# eth2dmx.net
KiCad netlist of a schematic drawn in EAGLE
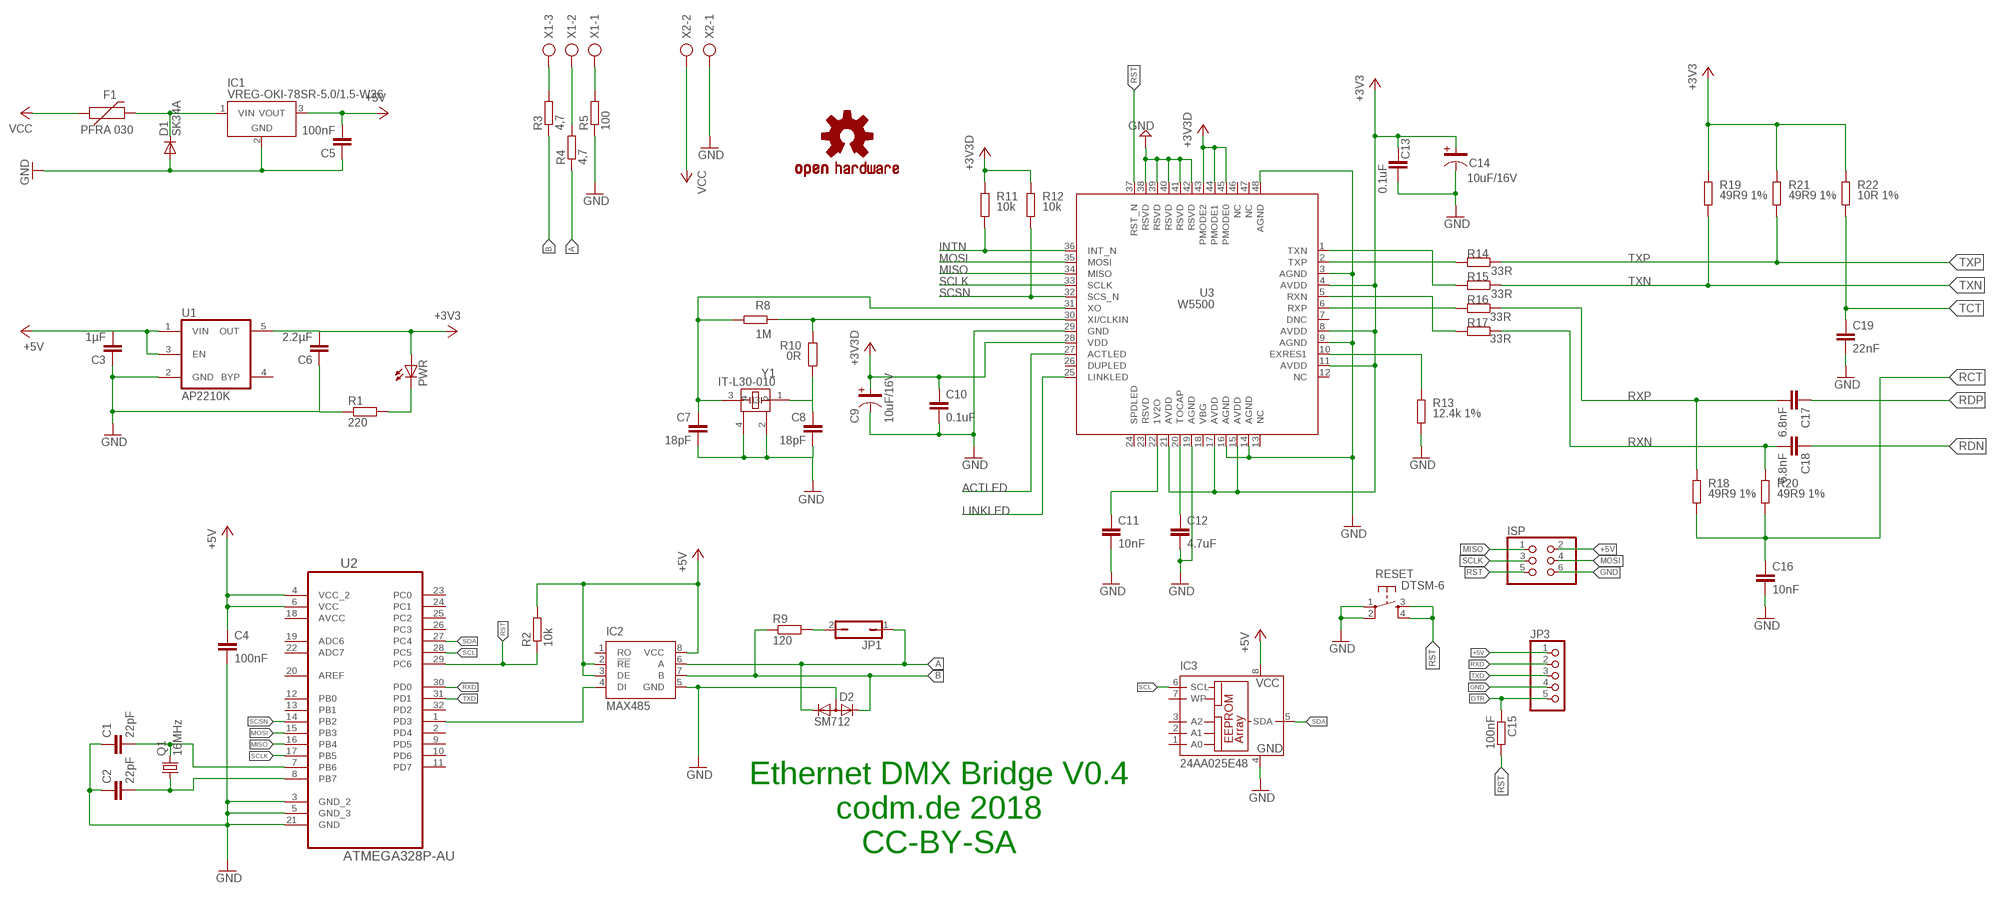
[diagram p0: schematic, sheet 1, part 1 of 2]
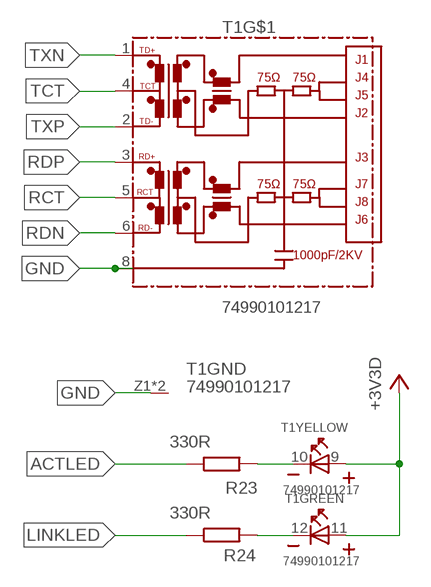
[diagram p1: schematic, sheet 1, part 2 of 2]

(export (version "E")
  (design (tool "Eeschema 10.0.6"))
  (components
    (comp (ref "C1")
      (value "22pF")
      (footprint "eagle-import:C0805")
      (libsource (lib "eagle-import") (part "C-EUC0805"))
    )
    (comp (ref "C2")
      (value "22pF")
      (footprint "eagle-import:C0805")
      (libsource (lib "eagle-import") (part "C-EUC0805"))
    )
    (comp (ref "C3")
      (value "1µF")
      (footprint "eagle-import:C0805")
      (libsource (lib "eagle-import") (part "C-EUC0805"))
    )
    (comp (ref "C4")
      (value "100nF")
      (footprint "eagle-import:C0805")
      (libsource (lib "eagle-import") (part "C-EUC0805"))
    )
    (comp (ref "C5")
      (value "100nF")
      (footprint "eagle-import:C0805")
      (libsource (lib "eagle-import") (part "C-EUC0805"))
    )
    (comp (ref "C6")
      (value "2.2µF")
      (footprint "eagle-import:C0805")
      (libsource (lib "eagle-import") (part "C-EUC0805"))
    )
    (comp (ref "C7")
      (value "18pF")
      (footprint "eagle-import:C0805")
      (libsource (lib "eagle-import") (part "C-EUC0805"))
    )
    (comp (ref "C8")
      (value "18pF")
      (footprint "eagle-import:C0805")
      (libsource (lib "eagle-import") (part "C-EUC0805"))
    )
    (comp (ref "C9")
      (value "10uF/16V")
      (footprint "eagle-import:C-3216(TANTAL)")
      (libsource (lib "eagle-import") (part "C-3216(TANTAL)"))
    )
    (comp (ref "C10")
      (value "0.1uF")
      (footprint "eagle-import:C0805")
      (libsource (lib "eagle-import") (part "C-EUC0805"))
    )
    (comp (ref "C11")
      (value "10nF")
      (footprint "eagle-import:C0805")
      (libsource (lib "eagle-import") (part "C-EUC0805"))
    )
    (comp (ref "C12")
      (value "4.7uF")
      (footprint "eagle-import:C0805")
      (libsource (lib "eagle-import") (part "C-EUC0805"))
    )
    (comp (ref "C13")
      (value "0.1uF")
      (footprint "eagle-import:C0805")
      (libsource (lib "eagle-import") (part "C-EUC0805"))
    )
    (comp (ref "C14")
      (value "10uF/16V")
      (footprint "eagle-import:C-3216(TANTAL)")
      (libsource (lib "eagle-import") (part "C-3216(TANTAL)"))
    )
    (comp (ref "C15")
      (value "100nF")
      (footprint "eagle-import:R0805")
      (libsource (lib "eagle-import") (part "R-EU_R0805"))
    )
    (comp (ref "C16")
      (value "10nF")
      (footprint "eagle-import:C0805")
      (libsource (lib "eagle-import") (part "C-EUC0805"))
    )
    (comp (ref "C17")
      (value "6.8nF")
      (footprint "eagle-import:C0805")
      (libsource (lib "eagle-import") (part "C-EUC0805"))
    )
    (comp (ref "C18")
      (value "6.8nF")
      (footprint "eagle-import:C0805")
      (libsource (lib "eagle-import") (part "C-EUC0805"))
    )
    (comp (ref "C19")
      (value "22nF")
      (footprint "eagle-import:C0805")
      (libsource (lib "eagle-import") (part "C-EUC0805"))
    )
    (comp (ref "D1")
      (value "SK34A")
      (footprint "eagle-import:DO214AC")
      (libsource (lib "eagle-import") (part "DIODE-DO214AC"))
    )
    (comp (ref "D2")
      (value "SM712")
      (footprint "eagle-import:SOT23")
      (libsource (lib "eagle-import") (part "DIODE-2CA|ACSOT23"))
    )
    (comp (ref "F1")
      (value "PFRA 030")
      (footprint "eagle-import:PTH")
      (libsource (lib "eagle-import") (part "PPTC_PTH"))
    )
    (comp (ref "IC1")
      (value "VREG-OKI-78SR-5.0/1.5-W36")
      (footprint "eagle-import:OKI-78SR")
      (libsource (lib "eagle-import") (part "VREG-OKI-78SR-5.0/1.5-W36"))
    )
    (comp (ref "IC2")
      (value "MAX485")
      (footprint "eagle-import:SOIC8")
      (libsource (lib "eagle-import") (part "LTC485S"))
    )
    (comp (ref "IC3")
      (value "24AA025E48")
      (footprint "eagle-import:SO-08")
      (fields (field (name "MPN") "24AA02/SN"))
      (libsource (lib "eagle-import") (part "24SNAA02"))
    )
    (comp (ref "ISP")
      (value "PINHD-2X3")
      (footprint "eagle-import:2X03")
      (libsource (lib "eagle-import") (part "PINHD-2X3"))
    )
    (comp (ref "JP1")
      (value "JP1Q")
      (footprint "eagle-import:JP1")
      (libsource (lib "eagle-import") (part "JP1Q"))
    )
    (comp (ref "JP3")
      (value "PINHD-1X5")
      (footprint "eagle-import:1X05")
      (libsource (lib "eagle-import") (part "PINHD-1X5"))
    )
    (comp (ref "LOGO1")
      (value "OSHW-LOGOM")
      (footprint "eagle-import:OSHW-LOGO-M")
      (libsource (lib "eagle-import") (part "OSHW-LOGOM"))
    )
    (comp (ref "PWR")
      (value "LEDCHIP-LED0805")
      (footprint "eagle-import:CHIP-LED0805")
      (libsource (lib "eagle-import") (part "LEDCHIP-LED0805"))
    )
    (comp (ref "Q1")
      (value "16MHz")
      (footprint "eagle-import:HC49U70")
      (libsource (lib "eagle-import") (part "CRYSTALHC49U70"))
    )
    (comp (ref "R1")
      (value "220")
      (footprint "eagle-import:R0805")
      (libsource (lib "eagle-import") (part "R-EU_R0805"))
    )
    (comp (ref "R2")
      (value "10k")
      (footprint "eagle-import:R0805")
      (libsource (lib "eagle-import") (part "R-EU_R0805"))
    )
    (comp (ref "R3")
      (value "4,7")
      (footprint "eagle-import:R0805")
      (libsource (lib "eagle-import") (part "R-EU_R0805"))
    )
    (comp (ref "R4")
      (value "4,7")
      (footprint "eagle-import:R0805")
      (libsource (lib "eagle-import") (part "R-EU_R0805"))
    )
    (comp (ref "R5")
      (value "100")
      (footprint "eagle-import:R0805")
      (libsource (lib "eagle-import") (part "R-EU_R0805"))
    )
    (comp (ref "R8")
      (value "1M")
      (footprint "eagle-import:R0805")
      (libsource (lib "eagle-import") (part "R-EU_R0805"))
    )
    (comp (ref "R9")
      (value "120")
      (footprint "eagle-import:R0805")
      (libsource (lib "eagle-import") (part "R-EU_R0805"))
    )
    (comp (ref "R10")
      (value "0R")
      (footprint "eagle-import:R0805")
      (libsource (lib "eagle-import") (part "R-EU_R0805"))
    )
    (comp (ref "R11")
      (value "10k")
      (footprint "eagle-import:R0805")
      (libsource (lib "eagle-import") (part "R-EU_R0805"))
    )
    (comp (ref "R12")
      (value "10k")
      (footprint "eagle-import:R0805")
      (libsource (lib "eagle-import") (part "R-EU_R0805"))
    )
    (comp (ref "R13")
      (value "12.4k 1%")
      (footprint "eagle-import:R0805")
      (libsource (lib "eagle-import") (part "R-EU_R0805"))
    )
    (comp (ref "R14")
      (value "33R")
      (footprint "eagle-import:R0805")
      (libsource (lib "eagle-import") (part "R-EU_R0805"))
    )
    (comp (ref "R15")
      (value "33R")
      (footprint "eagle-import:R0805")
      (libsource (lib "eagle-import") (part "R-EU_R0805"))
    )
    (comp (ref "R16")
      (value "33R")
      (footprint "eagle-import:R0805")
      (libsource (lib "eagle-import") (part "R-EU_R0805"))
    )
    (comp (ref "R17")
      (value "33R")
      (footprint "eagle-import:R0805")
      (libsource (lib "eagle-import") (part "R-EU_R0805"))
    )
    (comp (ref "R18")
      (value "49R9 1%")
      (footprint "eagle-import:R0805")
      (libsource (lib "eagle-import") (part "R-EU_R0805"))
    )
    (comp (ref "R19")
      (value "49R9 1%")
      (footprint "eagle-import:R0805")
      (libsource (lib "eagle-import") (part "R-EU_R0805"))
    )
    (comp (ref "R20")
      (value "49R9 1%")
      (footprint "eagle-import:R0805")
      (libsource (lib "eagle-import") (part "R-EU_R0805"))
    )
    (comp (ref "R21")
      (value "49R9 1%")
      (footprint "eagle-import:R0805")
      (libsource (lib "eagle-import") (part "R-EU_R0805"))
    )
    (comp (ref "R22")
      (value "10R 1%")
      (footprint "eagle-import:R0805")
      (libsource (lib "eagle-import") (part "R-EU_R0805"))
    )
    (comp (ref "R23")
      (value "330R")
      (footprint "eagle-import:R0805")
      (libsource (lib "eagle-import") (part "R-EU_R0805"))
    )
    (comp (ref "R24")
      (value "330R")
      (footprint "eagle-import:R0805")
      (libsource (lib "eagle-import") (part "R-EU_R0805"))
    )
    (comp (ref "RESET")
      (value "DTSM-6")
      (footprint "eagle-import:DTSM-6")
      (libsource (lib "eagle-import") (part "DTSM-6"))
    )
    (comp (ref "T1")
      (value "74990101217")
      (footprint "eagle-import:74990111217")
      (libsource (lib "eagle-import") (part "WE-RJ45_74990111217"))
    )
    (comp (ref "U1")
      (value "AP2210K")
      (footprint "eagle-import:SOT23-5")
      (libsource (lib "eagle-import") (part "AP2210K"))
    )
    (comp (ref "U2")
      (value "ATMEGA328P-AU")
      (footprint "eagle-import:QFP80P900X900X120-32N")
      (libsource (lib "eagle-import") (part "ATMEGA328P-AU"))
    )
    (comp (ref "U3")
      (value "W5500")
      (footprint "eagle-import:W5500")
      (libsource (lib "eagle-import") (part "W5500"))
    )
    (comp (ref "X1")
      (value "AK500/3")
      (footprint "eagle-import:AK500_3")
      (libsource (lib "eagle-import") (part "AK500/3"))
    )
    (comp (ref "X2")
      (value "AK500/2")
      (footprint "eagle-import:AK500_2")
      (libsource (lib "eagle-import") (part "AK500/2"))
    )
    (comp (ref "Y1")
      (value "IT-L30-010")
      (footprint "eagle-import:IT-L30-010")
      (libsource (lib "eagle-import") (part "IT-L30-010"))
    )
  )
  (nets
    (net (code "1") (name "+3V3") (class "Default")
      (node (ref "C10") (pin "1") (pinfunction "1_1") (pintype "passive"))
      (node (ref "C13") (pin "1") (pinfunction "1_1") (pintype "passive"))
      (node (ref "C14") (pin "1") (pinfunction "1_1") (pintype "passive"))
      (node (ref "C6") (pin "2") (pinfunction "2_2") (pintype "passive"))
      (node (ref "C9") (pin "1") (pinfunction "1_1") (pintype "passive"))
      (node (ref "PWR") (pin "A") (pinfunction "A_A") (pintype "passive"))
      (node (ref "R11") (pin "2") (pinfunction "2_2") (pintype "passive"))
      (node (ref "R12") (pin "2") (pinfunction "2_2") (pintype "passive"))
      (node (ref "R19") (pin "2") (pinfunction "2_2") (pintype "passive"))
      (node (ref "R21") (pin "2") (pinfunction "2_2") (pintype "passive"))
      (node (ref "R22") (pin "2") (pinfunction "2_2") (pintype "passive"))
      (node (ref "T1") (pin "11") (pinfunction "A_11") (pintype "passive"))
      (node (ref "T1") (pin "9") (pinfunction "A_9") (pintype "passive"))
      (node (ref "U1") (pin "5") (pinfunction "OUT_5") (pintype "power_in"))
      (node (ref "U3") (pin "11") (pinfunction "AVDD_11") (pintype "passive"))
      (node (ref "U3") (pin "15") (pinfunction "AVDD_15") (pintype "passive"))
      (node (ref "U3") (pin "17") (pinfunction "AVDD_17") (pintype "passive"))
      (node (ref "U3") (pin "21") (pinfunction "AVDD_21") (pintype "passive"))
      (node (ref "U3") (pin "28") (pinfunction "VDD_28") (pintype "passive"))
      (node (ref "U3") (pin "4") (pinfunction "AVDD_4") (pintype "passive"))
      (node (ref "U3") (pin "43") (pinfunction "PMODE2_43") (pintype "passive"))
      (node (ref "U3") (pin "44") (pinfunction "PMODE1_44") (pintype "passive"))
      (node (ref "U3") (pin "45") (pinfunction "PMODE0_45") (pintype "passive"))
      (node (ref "U3") (pin "8") (pinfunction "AVDD_8") (pintype "passive"))
    )
    (net (code "2") (name "+5V") (class "Default")
      (node (ref "C3") (pin "2") (pinfunction "2_2") (pintype "passive"))
      (node (ref "C4") (pin "1") (pinfunction "1_1") (pintype "passive"))
      (node (ref "C5") (pin "2") (pinfunction "2_2") (pintype "passive"))
      (node (ref "IC1") (pin "3") (pinfunction "VOUT_3") (pintype "power_in"))
      (node (ref "IC2") (pin "2") (pinfunction "~{RE}_2") (pintype "input"))
      (node (ref "IC2") (pin "3") (pinfunction "DE_3") (pintype "input"))
      (node (ref "IC2") (pin "8") (pinfunction "VCC_8") (pintype "input"))
      (node (ref "IC3") (pin "8") (pinfunction "VCC_8") (pintype "power_in"))
      (node (ref "ISP") (pin "2") (pinfunction "2_2") (pintype "passive"))
      (node (ref "JP3") (pin "1") (pinfunction "1_1") (pintype "passive"))
      (node (ref "R2") (pin "2") (pinfunction "2_2") (pintype "passive"))
      (node (ref "U1") (pin "1") (pinfunction "VIN_1") (pintype "input"))
      (node (ref "U1") (pin "3") (pinfunction "EN_3") (pintype "input"))
      (node (ref "U2") (pin "4") (pinfunction "VCC_2_4") (pintype "power_in"))
      (node (ref "U2") (pin "6") (pinfunction "VCC_6") (pintype "power_in"))
    )
    (net (code "3") (name "/AVCC") (class "Default")
      (node (ref "U2") (pin "18") (pinfunction "AVCC_18") (pintype "power_in"))
    )
    (net (code "4") (name "/INTN") (class "Default")
      (node (ref "R11") (pin "1") (pinfunction "1_1") (pintype "passive"))
      (node (ref "U3") (pin "36") (pinfunction "INT_N_36") (pintype "passive"))
    )
    (net (code "5") (name "/RXN") (class "Default")
      (node (ref "C18") (pin "2") (pinfunction "2_2") (pintype "passive"))
      (node (ref "R17") (pin "1") (pinfunction "1_1") (pintype "passive"))
      (node (ref "R20") (pin "2") (pinfunction "2_2") (pintype "passive"))
    )
    (net (code "6") (name "/RXP") (class "Default")
      (node (ref "C17") (pin "2") (pinfunction "2_2") (pintype "passive"))
      (node (ref "R16") (pin "1") (pinfunction "1_1") (pintype "passive"))
      (node (ref "R18") (pin "2") (pinfunction "2_2") (pintype "passive"))
    )
    (net (code "7") (name "A") (class "Default")
      (node (ref "D2") (pin "1") (pinfunction "K1_1") (pintype "passive"))
      (node (ref "IC2") (pin "6") (pinfunction "A_6") (pintype "bidirectional"))
      (node (ref "JP1") (pin "1") (pinfunction "1_1") (pintype "passive"))
      (node (ref "R4") (pin "1") (pinfunction "1_1") (pintype "passive"))
    )
    (net (code "8") (name "ACTLED") (class "Default")
      (node (ref "R23") (pin "1") (pinfunction "1_1") (pintype "passive"))
      (node (ref "U3") (pin "27") (pinfunction "ACTLED_27") (pintype "passive"))
    )
    (net (code "9") (name "B") (class "Default")
      (node (ref "D2") (pin "2") (pinfunction "K2_2") (pintype "passive"))
      (node (ref "IC2") (pin "7") (pinfunction "B_7") (pintype "bidirectional"))
      (node (ref "R3") (pin "1") (pinfunction "1_1") (pintype "passive"))
      (node (ref "R9") (pin "1") (pinfunction "1_1") (pintype "passive"))
    )
    (net (code "10") (name "DTR") (class "Default")
      (node (ref "C15") (pin "1") (pinfunction "1_1") (pintype "passive"))
      (node (ref "JP3") (pin "5") (pinfunction "5_5") (pintype "passive"))
    )
    (net (code "11") (name "GND") (class "Default")
      (node (ref "C1") (pin "1") (pinfunction "1_1") (pintype "passive"))
      (node (ref "C10") (pin "2") (pinfunction "2_2") (pintype "passive"))
      (node (ref "C11") (pin "2") (pinfunction "2_2") (pintype "passive"))
      (node (ref "C12") (pin "2") (pinfunction "2_2") (pintype "passive"))
      (node (ref "C13") (pin "2") (pinfunction "2_2") (pintype "passive"))
      (node (ref "C14") (pin "2") (pinfunction "2_2") (pintype "passive"))
      (node (ref "C16") (pin "2") (pinfunction "2_2") (pintype "passive"))
      (node (ref "C19") (pin "2") (pinfunction "2_2") (pintype "passive"))
      (node (ref "C2") (pin "1") (pinfunction "1_1") (pintype "passive"))
      (node (ref "C3") (pin "1") (pinfunction "1_1") (pintype "passive"))
      (node (ref "C4") (pin "2") (pinfunction "2_2") (pintype "passive"))
      (node (ref "C5") (pin "1") (pinfunction "1_1") (pintype "passive"))
      (node (ref "C6") (pin "1") (pinfunction "1_1") (pintype "passive"))
      (node (ref "C7") (pin "2") (pinfunction "2_2") (pintype "passive"))
      (node (ref "C8") (pin "2") (pinfunction "2_2") (pintype "passive"))
      (node (ref "C9") (pin "2") (pinfunction "2_2") (pintype "passive"))
      (node (ref "D1") (pin "A") (pinfunction "A_A") (pintype "passive"))
      (node (ref "D2") (pin "3") (pinfunction "A_3") (pintype "passive"))
      (node (ref "IC1") (pin "2") (pinfunction "GND_2") (pintype "power_in"))
      (node (ref "IC2") (pin "5") (pinfunction "GND_5") (pintype "input"))
      (node (ref "IC3") (pin "4") (pinfunction "GND_4") (pintype "power_in"))
      (node (ref "ISP") (pin "6") (pinfunction "6_6") (pintype "passive"))
      (node (ref "JP3") (pin "4") (pinfunction "4_4") (pintype "passive"))
      (node (ref "R1") (pin "1") (pinfunction "1_1") (pintype "passive"))
      (node (ref "R13") (pin "1") (pinfunction "1_1") (pintype "passive"))
      (node (ref "R5") (pin "1") (pinfunction "1_1") (pintype "passive"))
      (node (ref "RESET") (pin "1") (pinfunction "1_1") (pintype "passive"))
      (node (ref "RESET") (pin "2") (pinfunction "2_2") (pintype "passive"))
      (node (ref "T1") (pin "8") (pinfunction "8_8") (pintype "bidirectional"))
      (node (ref "T1") (pin "Z1") (pinfunction "GND_Z1") (pintype "power_in"))
      (node (ref "T1") (pin "Z2") (pinfunction "GND_Z2") (pintype "power_in"))
      (node (ref "U1") (pin "2") (pinfunction "GND_2") (pintype "power_in"))
      (node (ref "U2") (pin "21") (pinfunction "GND_21") (pintype "passive"))
      (node (ref "U2") (pin "3") (pinfunction "GND_2_3") (pintype "passive"))
      (node (ref "U2") (pin "5") (pinfunction "GND_3_5") (pintype "passive"))
      (node (ref "U3") (pin "14") (pinfunction "AGND_14") (pintype "passive"))
      (node (ref "U3") (pin "16") (pinfunction "AGND_16") (pintype "passive"))
      (node (ref "U3") (pin "19") (pinfunction "AGND_19") (pintype "passive"))
      (node (ref "U3") (pin "29") (pinfunction "GND_29") (pintype "passive"))
      (node (ref "U3") (pin "3") (pinfunction "AGND_3") (pintype "passive"))
      (node (ref "U3") (pin "38") (pinfunction "RSVD_38") (pintype "passive"))
      (node (ref "U3") (pin "39") (pinfunction "RSVD_39") (pintype "passive"))
      (node (ref "U3") (pin "40") (pinfunction "RSVD_40") (pintype "passive"))
      (node (ref "U3") (pin "41") (pinfunction "RSVD_41") (pintype "passive"))
      (node (ref "U3") (pin "42") (pinfunction "RSVD_42") (pintype "passive"))
      (node (ref "U3") (pin "48") (pinfunction "AGND_48") (pintype "passive"))
      (node (ref "U3") (pin "9") (pinfunction "AGND_9") (pintype "passive"))
      (node (ref "X2") (pin "1") (pinfunction "KL_1") (pintype "passive"))
      (node (ref "Y1") (pin "2") (pinfunction "2_2") (pintype "passive"))
      (node (ref "Y1") (pin "4") (pinfunction "4_4") (pintype "passive"))
    )
    (net (code "12") (name "LINKLED") (class "Default")
      (node (ref "R24") (pin "1") (pinfunction "1_1") (pintype "passive"))
      (node (ref "U3") (pin "25") (pinfunction "LINKLED_25") (pintype "passive"))
    )
    (net (code "13") (name "MISO") (class "Default")
      (node (ref "ISP") (pin "1") (pinfunction "1_1") (pintype "passive"))
      (node (ref "U2") (pin "16") (pinfunction "PB4_16") (pintype "bidirectional"))
      (node (ref "U3") (pin "34") (pinfunction "MISO_34") (pintype "passive"))
    )
    (net (code "14") (name "MOSI") (class "Default")
      (node (ref "ISP") (pin "4") (pinfunction "4_4") (pintype "passive"))
      (node (ref "U2") (pin "15") (pinfunction "PB3_15") (pintype "bidirectional"))
      (node (ref "U3") (pin "35") (pinfunction "MOSI_35") (pintype "passive"))
    )
    (net (code "15") (name "Net-(C8-Pad1)") (class "Default")
      (node (ref "C8") (pin "1") (pinfunction "1_1") (pintype "passive"))
      (node (ref "R10") (pin "1") (pinfunction "1_1") (pintype "passive"))
      (node (ref "Y1") (pin "1") (pinfunction "1_1") (pintype "passive"))
    )
    (net (code "16") (name "Net-(F1-2)") (class "Default")
      (node (ref "D1") (pin "C") (pinfunction "C_C") (pintype "passive"))
      (node (ref "F1") (pin "P$2") (pinfunction "2_P$2") (pintype "bidirectional"))
      (node (ref "IC1") (pin "1") (pinfunction "VIN_1") (pintype "power_in"))
    )
    (net (code "17") (name "Net-(IC2-DI)") (class "Default")
      (node (ref "IC2") (pin "4") (pinfunction "DI_4") (pintype "input"))
      (node (ref "U2") (pin "1") (pinfunction "PD3_1") (pintype "bidirectional"))
    )
    (net (code "18") (name "Net-(JP1-Pad2)") (class "Default")
      (node (ref "JP1") (pin "2") (pinfunction "2_2") (pintype "passive"))
      (node (ref "R9") (pin "2") (pinfunction "2_2") (pintype "passive"))
    )
    (net (code "19") (name "Net-(PWR-PadC)") (class "Default")
      (node (ref "PWR") (pin "C") (pinfunction "C_C") (pintype "passive"))
      (node (ref "R1") (pin "2") (pinfunction "2_2") (pintype "passive"))
    )
    (net (code "20") (name "Net-(T1C-K)") (class "Default")
      (node (ref "R24") (pin "2") (pinfunction "2_2") (pintype "passive"))
      (node (ref "T1") (pin "12") (pinfunction "K_12") (pintype "passive"))
    )
    (net (code "21") (name "Net-(T1D-K)") (class "Default")
      (node (ref "R23") (pin "2") (pinfunction "2_2") (pintype "passive"))
      (node (ref "T1") (pin "10") (pinfunction "K_10") (pintype "passive"))
    )
    (net (code "22") (name "Net-(U2-PB6)") (class "Default")
      (node (ref "C1") (pin "2") (pinfunction "2_2") (pintype "passive"))
      (node (ref "Q1") (pin "2") (pinfunction "2_2") (pintype "passive"))
      (node (ref "U2") (pin "7") (pinfunction "PB6_7") (pintype "bidirectional"))
    )
    (net (code "23") (name "Net-(U2-PB7)") (class "Default")
      (node (ref "C2") (pin "2") (pinfunction "2_2") (pintype "passive"))
      (node (ref "Q1") (pin "1") (pinfunction "1_1") (pintype "passive"))
      (node (ref "U2") (pin "8") (pinfunction "PB7_8") (pintype "bidirectional"))
    )
    (net (code "24") (name "Net-(U3-1V2O)") (class "Default")
      (node (ref "C11") (pin "1") (pinfunction "1_1") (pintype "passive"))
      (node (ref "U3") (pin "22") (pinfunction "1V2O_22") (pintype "passive"))
    )
    (net (code "25") (name "Net-(U3-EXRES1)") (class "Default")
      (node (ref "R13") (pin "2") (pinfunction "2_2") (pintype "passive"))
      (node (ref "U3") (pin "10") (pinfunction "EXRES1_10") (pintype "passive"))
    )
    (net (code "26") (name "Net-(U3-RXN)") (class "Default")
      (node (ref "R17") (pin "2") (pinfunction "2_2") (pintype "passive"))
      (node (ref "U3") (pin "5") (pinfunction "RXN_5") (pintype "passive"))
    )
    (net (code "27") (name "Net-(U3-RXP)") (class "Default")
      (node (ref "R16") (pin "2") (pinfunction "2_2") (pintype "passive"))
      (node (ref "U3") (pin "6") (pinfunction "RXP_6") (pintype "passive"))
    )
    (net (code "28") (name "Net-(U3-TOCAP)") (class "Default")
      (node (ref "C12") (pin "1") (pinfunction "1_1") (pintype "passive"))
      (node (ref "U3") (pin "20") (pinfunction "TOCAP_20") (pintype "passive"))
    )
    (net (code "29") (name "Net-(U3-TXN)") (class "Default")
      (node (ref "R15") (pin "2") (pinfunction "2_2") (pintype "passive"))
      (node (ref "U3") (pin "1") (pinfunction "TXN_1") (pintype "passive"))
    )
    (net (code "30") (name "Net-(U3-TXP)") (class "Default")
      (node (ref "R14") (pin "2") (pinfunction "2_2") (pintype "passive"))
      (node (ref "U3") (pin "2") (pinfunction "TXP_2") (pintype "passive"))
    )
    (net (code "31") (name "Net-(U3-XI{slash}CLKIN)") (class "Default")
      (node (ref "R10") (pin "2") (pinfunction "2_2") (pintype "passive"))
      (node (ref "R8") (pin "2") (pinfunction "2_2") (pintype "passive"))
      (node (ref "U3") (pin "30") (pinfunction "XI/CLKIN_30") (pintype "passive"))
    )
    (net (code "32") (name "Net-(U3-XO)") (class "Default")
      (node (ref "C7") (pin "1") (pinfunction "1_1") (pintype "passive"))
      (node (ref "R8") (pin "1") (pinfunction "1_1") (pintype "passive"))
      (node (ref "U3") (pin "31") (pinfunction "XO_31") (pintype "passive"))
      (node (ref "Y1") (pin "3") (pinfunction "3_3") (pintype "passive"))
    )
    (net (code "33") (name "Net-(X1A-KL)") (class "Default")
      (node (ref "R5") (pin "2") (pinfunction "2_2") (pintype "passive"))
      (node (ref "X1") (pin "1") (pinfunction "KL_1") (pintype "passive"))
    )
    (net (code "34") (name "Net-(X1B-KL)") (class "Default")
      (node (ref "R4") (pin "2") (pinfunction "2_2") (pintype "passive"))
      (node (ref "X1") (pin "2") (pinfunction "KL_2") (pintype "passive"))
    )
    (net (code "35") (name "Net-(X1C-KL)") (class "Default")
      (node (ref "R3") (pin "2") (pinfunction "2_2") (pintype "passive"))
      (node (ref "X1") (pin "3") (pinfunction "KL_3") (pintype "passive"))
    )
    (net (code "36") (name "RCT") (class "Default")
      (node (ref "C16") (pin "1") (pinfunction "1_1") (pintype "passive"))
      (node (ref "R18") (pin "1") (pinfunction "1_1") (pintype "passive"))
      (node (ref "R20") (pin "1") (pinfunction "1_1") (pintype "passive"))
      (node (ref "T1") (pin "5") (pinfunction "RCT_5") (pintype "bidirectional"))
    )
    (net (code "37") (name "RDN") (class "Default")
      (node (ref "C18") (pin "1") (pinfunction "1_1") (pintype "passive"))
      (node (ref "T1") (pin "6") (pinfunction "RD-_6") (pintype "bidirectional"))
    )
    (net (code "38") (name "RDP") (class "Default")
      (node (ref "C17") (pin "1") (pinfunction "1_1") (pintype "passive"))
      (node (ref "T1") (pin "3") (pinfunction "RD+_3") (pintype "bidirectional"))
    )
    (net (code "39") (name "RST") (class "Default")
      (node (ref "C15") (pin "2") (pinfunction "2_2") (pintype "passive"))
      (node (ref "ISP") (pin "5") (pinfunction "5_5") (pintype "passive"))
      (node (ref "R2") (pin "1") (pinfunction "1_1") (pintype "passive"))
      (node (ref "RESET") (pin "3") (pinfunction "3_3") (pintype "passive"))
      (node (ref "RESET") (pin "4") (pinfunction "4_4") (pintype "passive"))
      (node (ref "U2") (pin "29") (pinfunction "PC6_29") (pintype "bidirectional"))
      (node (ref "U3") (pin "37") (pinfunction "RST_N_37") (pintype "passive"))
    )
    (net (code "40") (name "RXD") (class "Default")
      (node (ref "JP3") (pin "2") (pinfunction "2_2") (pintype "passive"))
      (node (ref "U2") (pin "30") (pinfunction "PD0_30") (pintype "bidirectional"))
    )
    (net (code "41") (name "SCL") (class "Default")
      (node (ref "IC3") (pin "6") (pinfunction "SCL_6") (pintype "input"))
      (node (ref "U2") (pin "28") (pinfunction "PC5_28") (pintype "bidirectional"))
    )
    (net (code "42") (name "SCLK") (class "Default")
      (node (ref "ISP") (pin "3") (pinfunction "3_3") (pintype "passive"))
      (node (ref "U2") (pin "17") (pinfunction "PB5_17") (pintype "bidirectional"))
      (node (ref "U3") (pin "33") (pinfunction "SCLK_33") (pintype "passive"))
    )
    (net (code "43") (name "SCSN") (class "Default")
      (node (ref "R12") (pin "1") (pinfunction "1_1") (pintype "passive"))
      (node (ref "U2") (pin "14") (pinfunction "PB2_14") (pintype "bidirectional"))
      (node (ref "U3") (pin "32") (pinfunction "SCS_N_32") (pintype "passive"))
    )
    (net (code "44") (name "SDA") (class "Default")
      (node (ref "IC3") (pin "5") (pinfunction "SDA_5") (pintype "bidirectional"))
      (node (ref "U2") (pin "27") (pinfunction "PC4_27") (pintype "bidirectional"))
    )
    (net (code "45") (name "TCT") (class "Default")
      (node (ref "C19") (pin "1") (pinfunction "1_1") (pintype "passive"))
      (node (ref "R22") (pin "1") (pinfunction "1_1") (pintype "passive"))
      (node (ref "T1") (pin "4") (pinfunction "TCT_4") (pintype "bidirectional"))
    )
    (net (code "46") (name "TXD") (class "Default")
      (node (ref "JP3") (pin "3") (pinfunction "3_3") (pintype "passive"))
      (node (ref "U2") (pin "31") (pinfunction "PD1_31") (pintype "bidirectional"))
    )
    (net (code "47") (name "TXN") (class "Default")
      (node (ref "R15") (pin "1") (pinfunction "1_1") (pintype "passive"))
      (node (ref "R19") (pin "1") (pinfunction "1_1") (pintype "passive"))
      (node (ref "T1") (pin "1") (pinfunction "TD+_1") (pintype "bidirectional"))
    )
    (net (code "48") (name "TXP") (class "Default")
      (node (ref "R14") (pin "1") (pinfunction "1_1") (pintype "passive"))
      (node (ref "R21") (pin "1") (pinfunction "1_1") (pintype "passive"))
      (node (ref "T1") (pin "2") (pinfunction "TD-_2") (pintype "bidirectional"))
    )
    (net (code "49") (name "VCC") (class "Default")
      (node (ref "F1") (pin "P$1") (pinfunction "1_P$1") (pintype "bidirectional"))
      (node (ref "X2") (pin "2") (pinfunction "KL_2") (pintype "passive"))
    )
    (net (code "50") (name "unconnected-(IC2-RO-Pad1)") (class "Default")
      (node (ref "IC2") (pin "1") (pinfunction "RO_1") (pintype "output"))
    )
    (net (code "51") (name "unconnected-(IC3-A0-Pad1)") (class "Default")
      (node (ref "IC3") (pin "1") (pinfunction "A0_1") (pintype "input"))
    )
    (net (code "52") (name "unconnected-(IC3-A1-Pad2)") (class "Default")
      (node (ref "IC3") (pin "2") (pinfunction "A1_2") (pintype "input"))
    )
    (net (code "53") (name "unconnected-(IC3-A2-Pad3)") (class "Default")
      (node (ref "IC3") (pin "3") (pinfunction "A2_3") (pintype "input"))
    )
    (net (code "54") (name "unconnected-(IC3-WP-Pad7)") (class "Default")
      (node (ref "IC3") (pin "7") (pinfunction "WP_7") (pintype "input"))
    )
    (net (code "55") (name "unconnected-(U1-BYP-Pad4)") (class "Default")
      (node (ref "U1") (pin "4") (pinfunction "BYP_4") (pintype "output"))
    )
    (net (code "56") (name "unconnected-(U2-ADC6-Pad19)") (class "Default")
      (node (ref "U2") (pin "19") (pinfunction "ADC6_19") (pintype "input"))
    )
    (net (code "57") (name "unconnected-(U2-ADC7-Pad22)") (class "Default")
      (node (ref "U2") (pin "22") (pinfunction "ADC7_22") (pintype "input"))
    )
    (net (code "58") (name "unconnected-(U2-AREF-Pad20)") (class "Default")
      (node (ref "U2") (pin "20") (pinfunction "AREF_20") (pintype "input"))
    )
    (net (code "59") (name "unconnected-(U2-PB0-Pad12)") (class "Default")
      (node (ref "U2") (pin "12") (pinfunction "PB0_12") (pintype "bidirectional"))
    )
    (net (code "60") (name "unconnected-(U2-PB1-Pad13)") (class "Default")
      (node (ref "U2") (pin "13") (pinfunction "PB1_13") (pintype "bidirectional"))
    )
    (net (code "61") (name "unconnected-(U2-PC0-Pad23)") (class "Default")
      (node (ref "U2") (pin "23") (pinfunction "PC0_23") (pintype "bidirectional"))
    )
    (net (code "62") (name "unconnected-(U2-PC1-Pad24)") (class "Default")
      (node (ref "U2") (pin "24") (pinfunction "PC1_24") (pintype "bidirectional"))
    )
    (net (code "63") (name "unconnected-(U2-PC2-Pad25)") (class "Default")
      (node (ref "U2") (pin "25") (pinfunction "PC2_25") (pintype "bidirectional"))
    )
    (net (code "64") (name "unconnected-(U2-PC3-Pad26)") (class "Default")
      (node (ref "U2") (pin "26") (pinfunction "PC3_26") (pintype "bidirectional"))
    )
    (net (code "65") (name "unconnected-(U2-PD2-Pad32)") (class "Default")
      (node (ref "U2") (pin "32") (pinfunction "PD2_32") (pintype "bidirectional"))
    )
    (net (code "66") (name "unconnected-(U2-PD4-Pad2)") (class "Default")
      (node (ref "U2") (pin "2") (pinfunction "PD4_2") (pintype "bidirectional"))
    )
    (net (code "67") (name "unconnected-(U2-PD5-Pad9)") (class "Default")
      (node (ref "U2") (pin "9") (pinfunction "PD5_9") (pintype "bidirectional"))
    )
    (net (code "68") (name "unconnected-(U2-PD6-Pad10)") (class "Default")
      (node (ref "U2") (pin "10") (pinfunction "PD6_10") (pintype "bidirectional"))
    )
    (net (code "69") (name "unconnected-(U2-PD7-Pad11)") (class "Default")
      (node (ref "U2") (pin "11") (pinfunction "PD7_11") (pintype "bidirectional"))
    )
    (net (code "70") (name "unconnected-(U3-DNC-Pad7)") (class "Default")
      (node (ref "U3") (pin "7") (pinfunction "DNC_7") (pintype "passive"))
    )
    (net (code "71") (name "unconnected-(U3-DUPLED-Pad26)") (class "Default")
      (node (ref "U3") (pin "26") (pinfunction "DUPLED_26") (pintype "passive"))
    )
    (net (code "72") (name "unconnected-(U3-NC-Pad12)") (class "Default")
      (node (ref "U3") (pin "12") (pinfunction "NC_12") (pintype "passive"))
    )
    (net (code "73") (name "unconnected-(U3-NC-Pad13)") (class "Default")
      (node (ref "U3") (pin "13") (pinfunction "NC_13") (pintype "passive"))
    )
    (net (code "74") (name "unconnected-(U3-NC-Pad46)") (class "Default")
      (node (ref "U3") (pin "46") (pinfunction "NC_46") (pintype "passive"))
    )
    (net (code "75") (name "unconnected-(U3-NC-Pad47)") (class "Default")
      (node (ref "U3") (pin "47") (pinfunction "NC_47") (pintype "passive"))
    )
    (net (code "76") (name "unconnected-(U3-RSVD-Pad23)") (class "Default")
      (node (ref "U3") (pin "23") (pinfunction "RSVD_23") (pintype "passive"))
    )
    (net (code "77") (name "unconnected-(U3-SPDLED-Pad24)") (class "Default")
      (node (ref "U3") (pin "24") (pinfunction "SPDLED_24") (pintype "passive"))
    )
    (net (code "78") (name "unconnected-(U3-VBG-Pad18)") (class "Default")
      (node (ref "U3") (pin "18") (pinfunction "VBG_18") (pintype "passive"))
    )
  )
)
